# USB.net
KiCad netlist of a schematic drawn in Altium Designer
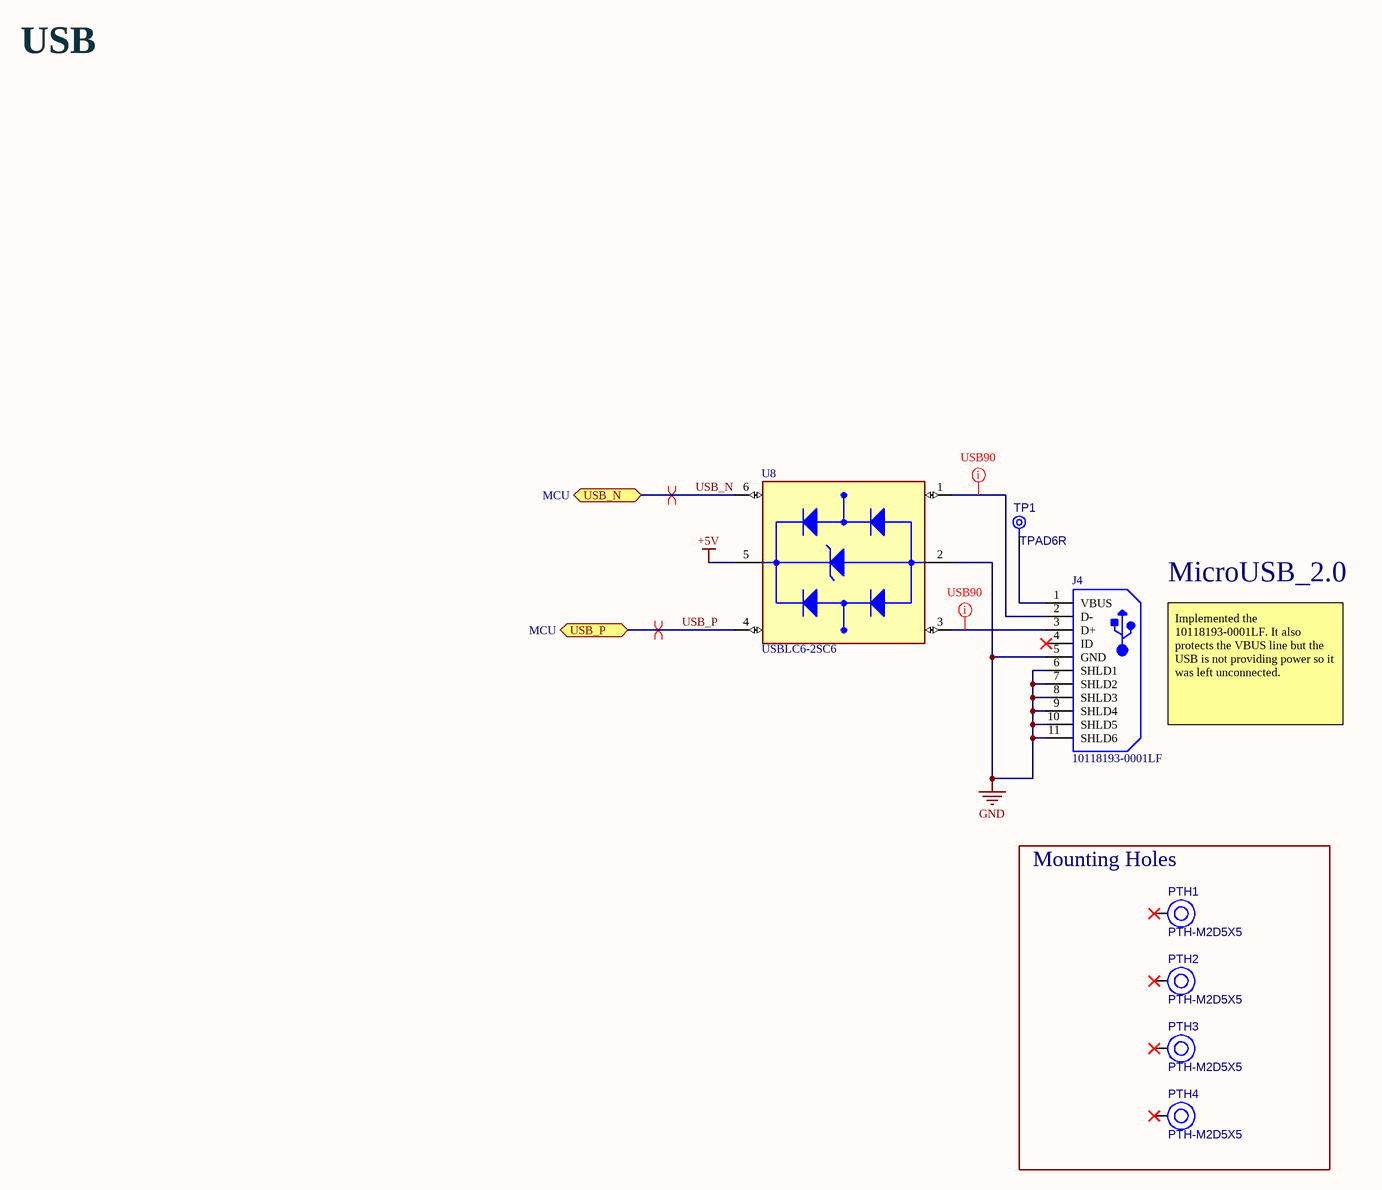
[diagram p0: USB.SchDoc]

(export (version "E")
  (design (tool "Eeschema 10.0.6"))
  (components
    (comp (ref "J4")
      (value "10118193-0001LF")
      (footprint "FCI-10118193-0001LF-5_V")
      (description "Micro USB B Type Receptacle, -55 to 85 degC, 5-Pin SMD, RoHS, Tape and Reel")
      (fields (field (name "MANUFACTURER") "FCI"))
      (libsource (lib "Altium Content Vault") (part "USB-5-6SHLD"))
    )
    (comp (ref "PTH1")
      (value "PTH-M2D5X5")
      (footprint "PTH-M2D5X5")
      (description "M2 PTH (2.5mm), 5mm pad")
      (libsource (lib "Personal Repository") (part "CMP-00028-00000-1"))
    )
    (comp (ref "PTH2")
      (value "PTH-M2D5X5")
      (footprint "PTH-M2D5X5")
      (description "M2 PTH (2.5mm), 5mm pad")
      (libsource (lib "Personal Repository") (part "CMP-00028-00000-1"))
    )
    (comp (ref "PTH3")
      (value "PTH-M2D5X5")
      (footprint "PTH-M2D5X5")
      (description "M2 PTH (2.5mm), 5mm pad")
      (libsource (lib "Personal Repository") (part "CMP-00028-00000-1"))
    )
    (comp (ref "PTH4")
      (value "PTH-M2D5X5")
      (footprint "PTH-M2D5X5")
      (description "M2 PTH (2.5mm), 5mm pad")
      (libsource (lib "Personal Repository") (part "CMP-00028-00000-1"))
    )
    (comp (ref "TP1")
      (value "TPAD6R")
      (footprint "TP06R")
      (description "0.6mm round")
      (libsource (lib "Personal Repository") (part "CMP-001-0001-4"))
    )
    (comp (ref "U8")
      (value "USBLC6-2SC6")
      (footprint "SOT95P280X145-6N")
      (description "17V Clamp 5A (8/20Âµs) Ipp Tvs Diode Surface Mount SOT-23-6")
      (fields (field (name "MF") "STMicroelectronics"))
      (libsource (lib "Personal Repository") (part "USBLC6-2SC6"))
    )
  )
  (nets
    (net (code "1") (name "+5V") (class "Default")
      (node (ref "U8") (pin "5") (pinfunction "VBUS_5") (pintype "power_in"))
    )
    (net (code "2") (name "/USB_N") (class "Default")
      (node (ref "U8") (pin "6") (pinfunction "I/O1_OUT_6") (pintype "bidirectional"))
    )
    (net (code "3") (name "/USB_P") (class "Default")
      (node (ref "U8") (pin "4") (pinfunction "I/O2_OUT_4") (pintype "bidirectional"))
    )
    (net (code "4") (name "GND") (class "Default")
      (node (ref "J4") (pin "10") (pinfunction "SHLD5_10") (pintype "passive"))
      (node (ref "J4") (pin "11") (pinfunction "SHLD6_11") (pintype "passive"))
      (node (ref "J4") (pin "5") (pinfunction "GND_5") (pintype "passive"))
      (node (ref "J4") (pin "6") (pinfunction "SHLD1_6") (pintype "passive"))
      (node (ref "J4") (pin "7") (pinfunction "SHLD2_7") (pintype "passive"))
      (node (ref "J4") (pin "8") (pinfunction "SHLD3_8") (pintype "passive"))
      (node (ref "J4") (pin "9") (pinfunction "SHLD4_9") (pintype "passive"))
      (node (ref "U8") (pin "2") (pinfunction "GND_2") (pintype "power_in"))
    )
    (net (code "5") (name "Net-(J4-D+)") (class "Default")
      (node (ref "J4") (pin "3") (pinfunction "D+_3") (pintype "passive"))
      (node (ref "U8") (pin "3") (pinfunction "I/O2_IN_3") (pintype "bidirectional"))
    )
    (net (code "6") (name "Net-(J4-D-)") (class "Default")
      (node (ref "J4") (pin "2") (pinfunction "D-_2") (pintype "passive"))
      (node (ref "U8") (pin "1") (pinfunction "I/O1_IN_1") (pintype "bidirectional"))
    )
    (net (code "7") (name "Net-(J4-VBUS)") (class "Default")
      (node (ref "J4") (pin "1") (pinfunction "VBUS_1") (pintype "passive"))
      (node (ref "TP1") (pin "1") (pinfunction "TP_1") (pintype "passive"))
    )
    (net (code "8") (name "unconnected-(J4-ID-Pad4)") (class "Default")
      (node (ref "J4") (pin "4") (pinfunction "ID_4") (pintype "passive+no_connect"))
    )
    (net (code "9") (name "unconnected-(PTH1-H1-Pad1)") (class "Default")
      (node (ref "PTH1") (pin "1") (pinfunction "H1_1") (pintype "passive+no_connect"))
    )
    (net (code "10") (name "unconnected-(PTH2-H1-Pad1)") (class "Default")
      (node (ref "PTH2") (pin "1") (pinfunction "H1_1") (pintype "passive+no_connect"))
    )
    (net (code "11") (name "unconnected-(PTH3-H1-Pad1)") (class "Default")
      (node (ref "PTH3") (pin "1") (pinfunction "H1_1") (pintype "passive+no_connect"))
    )
    (net (code "12") (name "unconnected-(PTH4-H1-Pad1)") (class "Default")
      (node (ref "PTH4") (pin "1") (pinfunction "H1_1") (pintype "passive+no_connect"))
    )
  )
)
